# Accumulator_Indicator_Light_r1.net
KiCad netlist of a schematic drawn in EAGLE
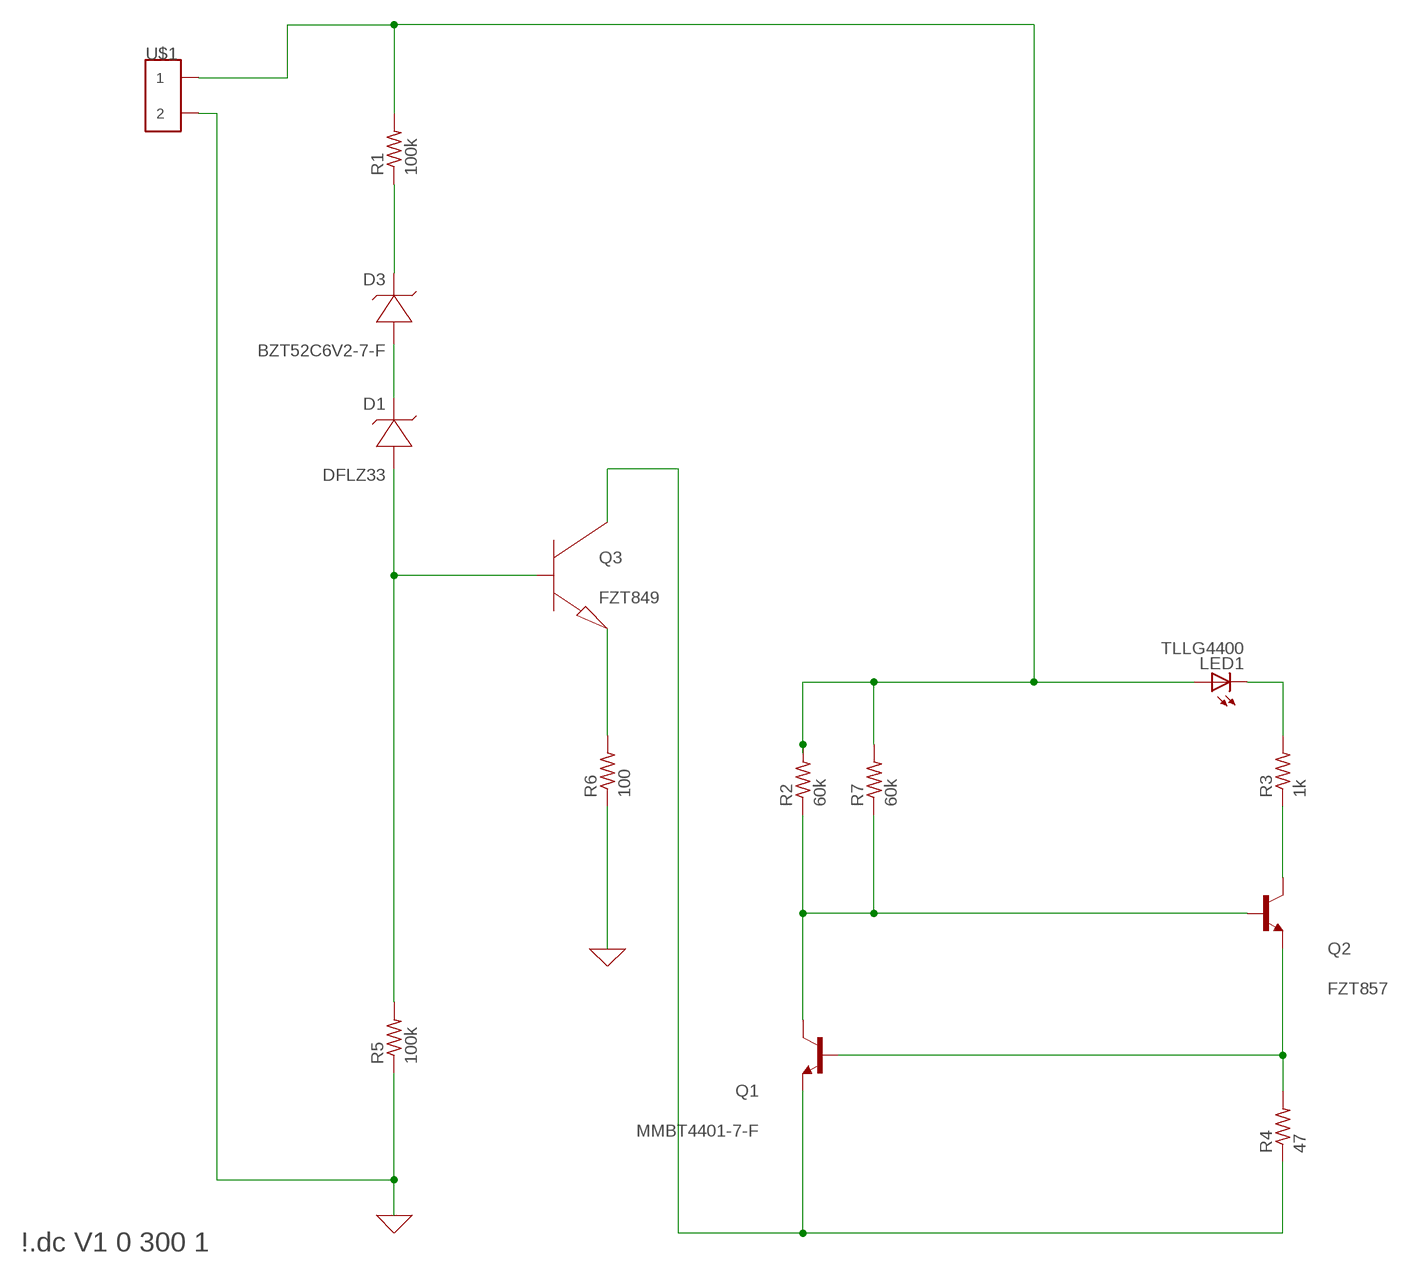
[diagram p0: schematic, sheet 1]

(export (version "E")
  (design (tool "Eeschema 10.0.6"))
  (components
    (comp (ref "D1")
      (value "DFLZ33")
      (footprint "eagle-import:SOD123")
      (libsource (lib "eagle-import") (part "ZENER"))
    )
    (comp (ref "D3")
      (value "BZT52C6V2-7-F")
      (footprint "eagle-import:SOD123")
      (libsource (lib "eagle-import") (part "ZENER"))
    )
    (comp (ref "LED1")
      (value "TLLG4400")
      (footprint "eagle-import:LED3MM")
      (fields (field (name "MF") "VISHAY SEMICONDUCTOR"))
      (libsource (lib "eagle-import") (part "TLLG4400"))
    )
    (comp (ref "Q1")
      (value "MMBT4401-7-F")
      (footprint "eagle-import:SOT-23-3")
      (libsource (lib "eagle-import") (part "MMBT4401-7-F"))
    )
    (comp (ref "Q2")
      (value "FZT857")
      (footprint "eagle-import:SOT223")
      (libsource (lib "eagle-import") (part "FZT857"))
    )
    (comp (ref "Q3")
      (value "FZT849")
      (footprint "eagle-import:SOT23")
      (libsource (lib "eagle-import") (part "NPN"))
    )
    (comp (ref "R1")
      (value "100k")
      (footprint "eagle-import:0411_15")
      (libsource (lib "eagle-import") (part "R-US_0411/15"))
    )
    (comp (ref "R2")
      (value "60k")
      (footprint "eagle-import:0411_15")
      (libsource (lib "eagle-import") (part "R-US_0411/15"))
    )
    (comp (ref "R3")
      (value "1k")
      (footprint "eagle-import:R0603")
      (libsource (lib "eagle-import") (part "resistor_R-US_R0603"))
    )
    (comp (ref "R4")
      (value "47")
      (footprint "eagle-import:R0603")
      (libsource (lib "eagle-import") (part "resistor_R-US_R0603"))
    )
    (comp (ref "R5")
      (value "100k")
      (footprint "eagle-import:R0603")
      (libsource (lib "eagle-import") (part "resistor_R-US_R0603"))
    )
    (comp (ref "R6")
      (value "100")
      (footprint "eagle-import:R0603")
      (libsource (lib "eagle-import") (part "resistor_R-US_R0603"))
    )
    (comp (ref "R7")
      (value "60k")
      (footprint "eagle-import:0411_15")
      (libsource (lib "eagle-import") (part "R-US_0411/15"))
    )
    (comp (ref "U$1")
      (value "CONN_2")
      (footprint "eagle-import:CONNECTOR_2")
      (libsource (lib "eagle-import") (part "CONN_2"))
    )
  )
  (nets
    (net (code "1") (name "0") (class "Default")
      (node (ref "R5") (pin "1") (pinfunction "1_1") (pintype "passive"))
      (node (ref "R6") (pin "1") (pinfunction "1_1") (pintype "passive"))
      (node (ref "U$1") (pin "3") (pinfunction "2_3") (pintype "bidirectional"))
      (node (ref "U$1") (pin "4") (pinfunction "2_4") (pintype "bidirectional"))
    )
    (net (code "2") (name "Net-(D1-+)") (class "Default")
      (node (ref "D1") (pin "A") (pinfunction "+_A") (pintype "passive"))
      (node (ref "Q3") (pin "2") (pinfunction "B_2") (pintype "passive"))
      (node (ref "R5") (pin "2") (pinfunction "2_2") (pintype "passive"))
    )
    (net (code "3") (name "Net-(D1--)") (class "Default")
      (node (ref "D1") (pin "C") (pinfunction "-_C") (pintype "passive"))
      (node (ref "D3") (pin "A") (pinfunction "+_A") (pintype "passive"))
    )
    (net (code "4") (name "Net-(D3--)") (class "Default")
      (node (ref "D3") (pin "C") (pinfunction "-_C") (pintype "passive"))
      (node (ref "R1") (pin "1") (pinfunction "1_1") (pintype "passive"))
    )
    (net (code "5") (name "Net-(LED1-C)") (class "Default")
      (node (ref "LED1") (pin "K") (pinfunction "C_K") (pintype "passive"))
      (node (ref "R3") (pin "2") (pinfunction "2_2") (pintype "passive"))
    )
    (net (code "6") (name "Net-(LED1-PadA)") (class "Default")
      (node (ref "LED1") (pin "A") (pinfunction "A_A") (pintype "passive"))
      (node (ref "R1") (pin "2") (pinfunction "2_2") (pintype "passive"))
      (node (ref "R2") (pin "2") (pinfunction "2_2") (pintype "passive"))
      (node (ref "R7") (pin "2") (pinfunction "2_2") (pintype "passive"))
      (node (ref "U$1") (pin "1") (pinfunction "1_1") (pintype "bidirectional"))
      (node (ref "U$1") (pin "2") (pinfunction "1_2") (pintype "bidirectional"))
    )
    (net (code "7") (name "Net-(Q1-B)") (class "Default")
      (node (ref "Q1") (pin "P$2") (pinfunction "B_P$2") (pintype "passive"))
      (node (ref "Q2") (pin "3") (pinfunction "E_3") (pintype "passive"))
      (node (ref "R4") (pin "2") (pinfunction "2_2") (pintype "passive"))
    )
    (net (code "8") (name "Net-(Q1-C)") (class "Default")
      (node (ref "Q1") (pin "P$1") (pinfunction "C_P$1") (pintype "passive"))
      (node (ref "Q2") (pin "1") (pinfunction "B_1") (pintype "passive"))
      (node (ref "R2") (pin "1") (pinfunction "1_1") (pintype "passive"))
      (node (ref "R7") (pin "1") (pinfunction "1_1") (pintype "passive"))
    )
    (net (code "9") (name "Net-(Q1-E)") (class "Default")
      (node (ref "Q1") (pin "P$3") (pinfunction "E_P$3") (pintype "passive"))
      (node (ref "Q3") (pin "3") (pinfunction "C_3") (pintype "passive"))
      (node (ref "R4") (pin "1") (pinfunction "1_1") (pintype "passive"))
    )
    (net (code "10") (name "Net-(Q2-C-Pad2)") (class "Default")
      (node (ref "Q2") (pin "2") (pinfunction "C_2") (pintype "passive"))
      (node (ref "Q2") (pin "4") (pinfunction "C_4") (pintype "passive"))
      (node (ref "R3") (pin "1") (pinfunction "1_1") (pintype "passive"))
    )
    (net (code "11") (name "Net-(Q3-E)") (class "Default")
      (node (ref "Q3") (pin "1") (pinfunction "E_1") (pintype "passive"))
      (node (ref "R6") (pin "2") (pinfunction "2_2") (pintype "passive"))
    )
  )
)
